# LDO.net
KiCad netlist of a schematic drawn in Altium Designer
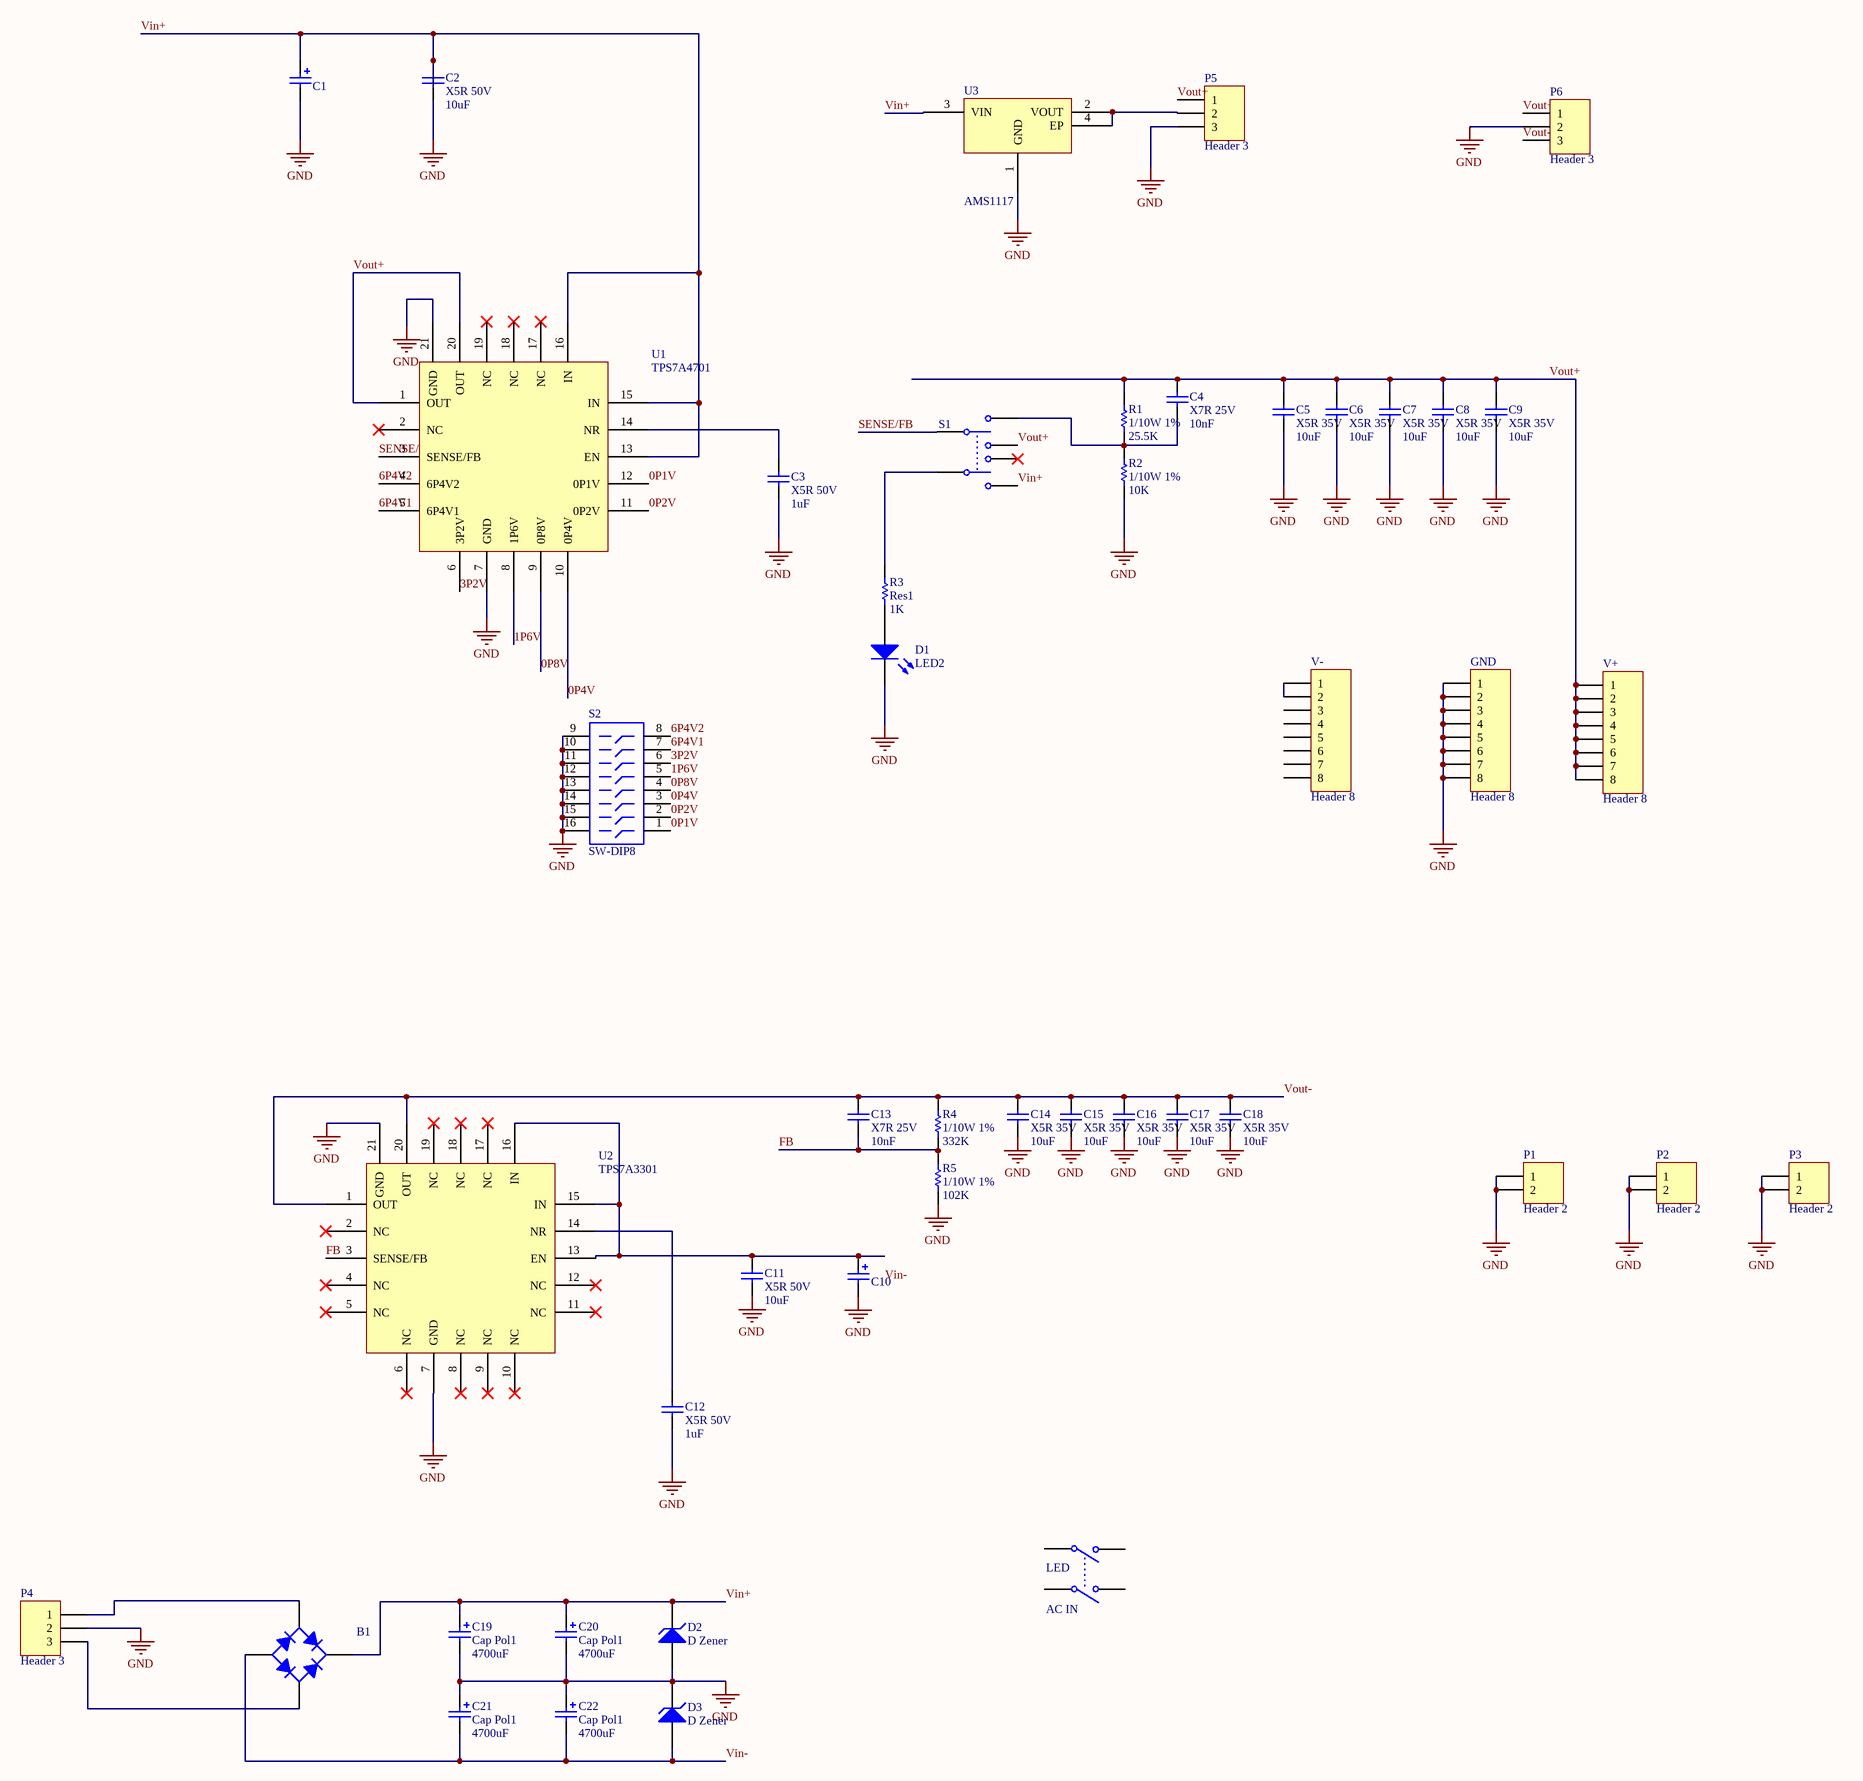
[diagram p0: LDO.SchDoc]

(export (version "E")
  (design (tool "Eeschema 10.0.6"))
  (components
    (comp (ref "AC IN")
      (value "SW AC 250V 6A")
      (footprint "SW AC 250V 6A")
      (libsource (lib "SMD") (part "SW AC 250V 6A"))
    )
    (comp (ref "B1")
      (value "Diode Bridge")
      (footprint "Diode Bridge")
      (libsource (lib "SMD") (part "Diode Bridge"))
    )
    (comp (ref "C1") (value "Tantalum") (footprint "D 7343-31") (libsource (lib "SMD") (part "Tantalum")))
    (comp (ref "C2")
      (value "X5R 50V")
      (footprint "C1206")
      (description "Capacitor (Semiconductor SIM Model)")
      (fields (field (name "ALTIUM_VALUE") "10uF") (field (name "PUBLISHER") "Altium Limited"))
      (libsource (lib "Miscellaneous Devices") (part "Cap Semi"))
    )
    (comp (ref "C3")
      (value "X5R 50V")
      (footprint "1608[0603]")
      (description "Capacitor")
      (fields (field (name "ALTIUM_VALUE") "1uF") (field (name "PUBLISHER") "Altium Limited"))
      (libsource (lib "Miscellaneous Devices") (part "Cap"))
    )
    (comp (ref "C4")
      (value "X7R 25V")
      (footprint "1608[0603]")
      (description "Capacitor")
      (fields (field (name "ALTIUM_VALUE") "10nF") (field (name "PUBLISHER") "Altium Limited"))
      (libsource (lib "Miscellaneous Devices") (part "Cap"))
    )
    (comp (ref "C5")
      (value "X5R 35V")
      (footprint "6-0805_N")
      (description "Capacitor")
      (fields (field (name "ALTIUM_VALUE") "10uF") (field (name "PUBLISHER") "Altium Limited"))
      (libsource (lib "Miscellaneous Devices") (part "Cap"))
    )
    (comp (ref "C6")
      (value "X5R 35V")
      (footprint "6-0805_N")
      (description "Capacitor")
      (fields (field (name "ALTIUM_VALUE") "10uF") (field (name "PUBLISHER") "Altium Limited"))
      (libsource (lib "Miscellaneous Devices") (part "Cap"))
    )
    (comp (ref "C7")
      (value "X5R 35V")
      (footprint "6-0805_N")
      (description "Capacitor")
      (fields (field (name "ALTIUM_VALUE") "10uF") (field (name "PUBLISHER") "Altium Limited"))
      (libsource (lib "Miscellaneous Devices") (part "Cap"))
    )
    (comp (ref "C8")
      (value "X5R 35V")
      (footprint "6-0805_N")
      (description "Capacitor")
      (fields (field (name "ALTIUM_VALUE") "10uF") (field (name "PUBLISHER") "Altium Limited"))
      (libsource (lib "Miscellaneous Devices") (part "Cap"))
    )
    (comp (ref "C9")
      (value "X5R 35V")
      (footprint "6-0805_N")
      (description "Capacitor")
      (fields (field (name "ALTIUM_VALUE") "10uF") (field (name "PUBLISHER") "Altium Limited"))
      (libsource (lib "Miscellaneous Devices") (part "Cap"))
    )
    (comp (ref "C10") (value "Tantalum") (footprint "D 7343-31") (libsource (lib "SMD") (part "Tantalum")))
    (comp (ref "C11")
      (value "X5R 50V")
      (footprint "C1206")
      (description "Capacitor (Semiconductor SIM Model)")
      (fields (field (name "ALTIUM_VALUE") "10uF") (field (name "PUBLISHER") "Altium Limited"))
      (libsource (lib "Miscellaneous Devices") (part "Cap Semi"))
    )
    (comp (ref "C12")
      (value "X5R 50V")
      (footprint "1608[0603]")
      (description "Capacitor")
      (fields (field (name "ALTIUM_VALUE") "1uF") (field (name "PUBLISHER") "Altium Limited"))
      (libsource (lib "Miscellaneous Devices") (part "Cap"))
    )
    (comp (ref "C13")
      (value "X7R 25V")
      (footprint "1608[0603]")
      (description "Capacitor")
      (fields (field (name "ALTIUM_VALUE") "10nF") (field (name "PUBLISHER") "Altium Limited"))
      (libsource (lib "Miscellaneous Devices") (part "Cap"))
    )
    (comp (ref "C14")
      (value "X5R 35V")
      (footprint "6-0805_N")
      (description "Capacitor")
      (fields (field (name "ALTIUM_VALUE") "10uF") (field (name "PUBLISHER") "Altium Limited"))
      (libsource (lib "Miscellaneous Devices") (part "Cap"))
    )
    (comp (ref "C15")
      (value "X5R 35V")
      (footprint "6-0805_N")
      (description "Capacitor")
      (fields (field (name "ALTIUM_VALUE") "10uF") (field (name "PUBLISHER") "Altium Limited"))
      (libsource (lib "Miscellaneous Devices") (part "Cap"))
    )
    (comp (ref "C16")
      (value "X5R 35V")
      (footprint "6-0805_N")
      (description "Capacitor")
      (fields (field (name "ALTIUM_VALUE") "10uF") (field (name "PUBLISHER") "Altium Limited"))
      (libsource (lib "Miscellaneous Devices") (part "Cap"))
    )
    (comp (ref "C17")
      (value "X5R 35V")
      (footprint "6-0805_N")
      (description "Capacitor")
      (fields (field (name "ALTIUM_VALUE") "10uF") (field (name "PUBLISHER") "Altium Limited"))
      (libsource (lib "Miscellaneous Devices") (part "Cap"))
    )
    (comp (ref "C18")
      (value "X5R 35V")
      (footprint "6-0805_N")
      (description "Capacitor")
      (fields (field (name "ALTIUM_VALUE") "10uF") (field (name "PUBLISHER") "Altium Limited"))
      (libsource (lib "Miscellaneous Devices") (part "Cap"))
    )
    (comp (ref "C19")
      (value "Cap Pol1")
      (footprint "RB7.6-15")
      (description "Polarized Capacitor (Radial)")
      (fields (field (name "ALTIUM_VALUE") "4700uF") (field (name "PUBLISHER") "Altium Limited"))
      (libsource (lib "Miscellaneous Devices") (part "Cap Pol1"))
    )
    (comp (ref "C20")
      (value "Cap Pol1")
      (footprint "RB7.6-15")
      (description "Polarized Capacitor (Radial)")
      (fields (field (name "ALTIUM_VALUE") "4700uF") (field (name "PUBLISHER") "Altium Limited"))
      (libsource (lib "Miscellaneous Devices") (part "Cap Pol1"))
    )
    (comp (ref "C21")
      (value "Cap Pol1")
      (footprint "RB7.6-15")
      (description "Polarized Capacitor (Radial)")
      (fields (field (name "ALTIUM_VALUE") "4700uF") (field (name "PUBLISHER") "Altium Limited"))
      (libsource (lib "Miscellaneous Devices") (part "Cap Pol1"))
    )
    (comp (ref "C22")
      (value "Cap Pol1")
      (footprint "RB7.6-15")
      (description "Polarized Capacitor (Radial)")
      (fields (field (name "ALTIUM_VALUE") "4700uF") (field (name "PUBLISHER") "Altium Limited"))
      (libsource (lib "Miscellaneous Devices") (part "Cap Pol1"))
    )
    (comp (ref "D1")
      (value "LED2")
      (footprint "6-0805_N")
      (description "Typical RED, GREEN, YELLOW, AMBER GaAs LED")
      (fields (field (name "PUBLISHER") "Altium Limited"))
      (libsource (lib "Miscellaneous Devices") (part "LED2"))
    )
    (comp (ref "D2")
      (value "D Zener")
      (footprint "AXIAL-0.3")
      (description "Zener Diode")
      (fields (field (name "PUBLISHER") "Altium Limited"))
      (libsource (lib "Miscellaneous Devices") (part "D Zener"))
    )
    (comp (ref "D3")
      (value "D Zener")
      (footprint "AXIAL-0.3")
      (description "Zener Diode")
      (fields (field (name "PUBLISHER") "Altium Limited"))
      (libsource (lib "Miscellaneous Devices") (part "D Zener"))
    )
    (comp (ref "GND")
      (value "Header 8")
      (footprint "HDR1X8")
      (description "Header, 8-Pin")
      (fields (field (name "PUBLISHER") "Altium Limited"))
      (libsource (lib "Miscellaneous Connectors") (part "Header 8"))
    )
    (comp (ref "P1")
      (value "Header 2")
      (footprint "HDR1X2")
      (description "Header, 2-Pin")
      (fields (field (name "PUBLISHER") "Altium Limited"))
      (libsource (lib "Miscellaneous Connectors") (part "Header 2"))
    )
    (comp (ref "P2")
      (value "Header 2")
      (footprint "HDR1X2")
      (description "Header, 2-Pin")
      (fields (field (name "PUBLISHER") "Altium Limited"))
      (libsource (lib "Miscellaneous Connectors") (part "Header 2"))
    )
    (comp (ref "P3")
      (value "Header 2")
      (footprint "HDR1X2")
      (description "Header, 2-Pin")
      (fields (field (name "PUBLISHER") "Altium Limited"))
      (libsource (lib "Miscellaneous Connectors") (part "Header 2"))
    )
    (comp (ref "P4")
      (value "Header 3")
      (footprint "HDR1X3")
      (description "Header, 3-Pin")
      (fields (field (name "PUBLISHER") "Altium Limited"))
      (libsource (lib "") (part "Header 3_1"))
    )
    (comp (ref "P5")
      (value "Header 3")
      (footprint "HDR1X3")
      (description "Header, 3-Pin")
      (fields (field (name "PUBLISHER") "Altium Limited"))
      (libsource (lib "Miscellaneous Connectors") (part "Header 3"))
    )
    (comp (ref "P6")
      (value "Header 3")
      (footprint "HDR1X3")
      (description "Header, 3-Pin")
      (fields (field (name "PUBLISHER") "Altium Limited"))
      (libsource (lib "Miscellaneous Connectors") (part "Header 3"))
    )
    (comp (ref "R1")
      (value "1/10W 1%")
      (footprint "1608[0603]")
      (description "Resistor")
      (fields (field (name "ALTIUM_VALUE") "25.5K") (field (name "PUBLISHER") "Altium Limited"))
      (libsource (lib "Miscellaneous Devices") (part "Res1"))
    )
    (comp (ref "R2")
      (value "1/10W 1%")
      (footprint "1608[0603]")
      (description "Resistor")
      (fields (field (name "ALTIUM_VALUE") "10K") (field (name "PUBLISHER") "Altium Limited"))
      (libsource (lib "Miscellaneous Devices") (part "Res1"))
    )
    (comp (ref "R3")
      (value "Res1")
      (footprint "6-0805_N")
      (description "Resistor")
      (fields (field (name "ALTIUM_VALUE") "1K") (field (name "PUBLISHER") "Altium Limited"))
      (libsource (lib "Miscellaneous Devices") (part "Res1"))
    )
    (comp (ref "R4")
      (value "1/10W 1%")
      (footprint "1608[0603]")
      (description "Resistor")
      (fields (field (name "ALTIUM_VALUE") "332K") (field (name "PUBLISHER") "Altium Limited"))
      (libsource (lib "Miscellaneous Devices") (part "Res1"))
    )
    (comp (ref "R5")
      (value "1/10W 1%")
      (footprint "1608[0603]")
      (description "Resistor")
      (fields (field (name "ALTIUM_VALUE") "102K") (field (name "PUBLISHER") "Altium Limited"))
      (libsource (lib "Miscellaneous Devices") (part "Res1"))
    )
    (comp (ref "S1") (value "SW  Press") (footprint "SW Press") (libsource (lib "SMD") (part "SW  Press")))
    (comp (ref "S2")
      (value "SW-DIP8")
      (footprint "DIP-16-KEY")
      (description "4009 Series DIP Switch, Raised actuator")
      (fields (field (name "PUBLISHER") "Altium Limited"))
      (libsource (lib "Miscellaneous Devices") (part "SW-DIP8"))
    )
    (comp (ref "U1")
      (value "TPS7A4701")
      (footprint "RGW 5×5 QFN-20")
      (libsource (lib "Created") (part "TPS7A4701RGWT"))
    )
    (comp (ref "U2")
      (value "TPS7A3301")
      (footprint "RGW 5×5 QFN-20")
      (libsource (lib "Created") (part "TPS7A3301RGWT"))
    )
    (comp (ref "U3") (value "AMS1117") (footprint "SOT223_N") (libsource (lib "Created") (part "AMS1117")))
    (comp (ref "V+")
      (value "Header 8")
      (footprint "HDR1X8")
      (description "Header, 8-Pin")
      (fields (field (name "PUBLISHER") "Altium Limited"))
      (libsource (lib "Miscellaneous Connectors") (part "Header 8"))
    )
    (comp (ref "V-")
      (value "Header 8")
      (footprint "HDR1X8")
      (description "Header, 8-Pin")
      (fields (field (name "PUBLISHER") "Altium Limited"))
      (libsource (lib "Miscellaneous Connectors") (part "Header 8"))
    )
  )
  (nets
    (net (code "1") (name "/0P1V") (class "Default")
      (node (ref "S2") (pin "1") (pinfunction "1_1") (pintype "passive"))
      (node (ref "U1") (pin "12") (pinfunction "0P1V_12") (pintype "passive"))
    )
    (net (code "2") (name "/0P2V") (class "Default")
      (node (ref "S2") (pin "2") (pinfunction "2_2") (pintype "passive"))
      (node (ref "U1") (pin "11") (pinfunction "0P2V_11") (pintype "passive"))
    )
    (net (code "3") (name "/0P4V") (class "Default")
      (node (ref "S2") (pin "3") (pinfunction "3_3") (pintype "passive"))
      (node (ref "U1") (pin "10") (pinfunction "0P4V_10") (pintype "passive"))
    )
    (net (code "4") (name "/0P8V") (class "Default")
      (node (ref "S2") (pin "4") (pinfunction "4_4") (pintype "passive"))
      (node (ref "U1") (pin "9") (pinfunction "0P8V_9") (pintype "passive"))
    )
    (net (code "5") (name "/1P6V") (class "Default")
      (node (ref "S2") (pin "5") (pinfunction "5_5") (pintype "passive"))
      (node (ref "U1") (pin "8") (pinfunction "1P6V_8") (pintype "passive"))
    )
    (net (code "6") (name "/3P2V") (class "Default")
      (node (ref "S2") (pin "6") (pinfunction "6_6") (pintype "passive"))
      (node (ref "U1") (pin "6") (pinfunction "3P2V_6") (pintype "passive"))
    )
    (net (code "7") (name "/6P4V1") (class "Default")
      (node (ref "S2") (pin "7") (pinfunction "7_7") (pintype "passive"))
      (node (ref "U1") (pin "5") (pinfunction "6P4V1_5") (pintype "passive"))
    )
    (net (code "8") (name "/6P4V2") (class "Default")
      (node (ref "S2") (pin "8") (pinfunction "8_8") (pintype "passive"))
      (node (ref "U1") (pin "4") (pinfunction "6P4V2_4") (pintype "passive"))
    )
    (net (code "9") (name "/FB") (class "Default")
      (node (ref "C13") (pin "1") (pinfunction "1_1") (pintype "passive"))
      (node (ref "R4") (pin "1") (pinfunction "1_1") (pintype "passive"))
      (node (ref "R5") (pin "2") (pinfunction "2_2") (pintype "passive"))
      (node (ref "U2") (pin "3") (pinfunction "SENSE/FB_3") (pintype "passive"))
    )
    (net (code "10") (name "/SENSE{slash}FB") (class "Default")
      (node (ref "S1") (pin "3") (pinfunction "3_3") (pintype "passive"))
      (node (ref "U1") (pin "3") (pinfunction "SENSE/FB_3") (pintype "passive"))
    )
    (net (code "11") (name "/Vin+") (class "Default")
      (node (ref "B1") (pin "4") (pinfunction "4_4") (pintype "passive"))
      (node (ref "C1") (pin "1") (pinfunction "1_1") (pintype "passive"))
      (node (ref "C19") (pin "1") (pinfunction "1_1") (pintype "passive"))
      (node (ref "C2") (pin "2") (pinfunction "2_2") (pintype "passive"))
      (node (ref "C20") (pin "1") (pinfunction "1_1") (pintype "passive"))
      (node (ref "D2") (pin "2") (pinfunction "K_2") (pintype "passive"))
      (node (ref "S1") (pin "5") (pinfunction "5_5") (pintype "passive"))
      (node (ref "U1") (pin "13") (pinfunction "EN_13") (pintype "passive"))
      (node (ref "U1") (pin "15") (pinfunction "IN_15") (pintype "passive"))
      (node (ref "U1") (pin "16") (pinfunction "IN_16") (pintype "passive"))
      (node (ref "U3") (pin "3") (pinfunction "VIN_3") (pintype "passive"))
    )
    (net (code "12") (name "/Vin-") (class "Default")
      (node (ref "B1") (pin "1") (pinfunction "1_1") (pintype "passive"))
      (node (ref "C21") (pin "2") (pinfunction "2_2") (pintype "passive"))
      (node (ref "C22") (pin "2") (pinfunction "2_2") (pintype "passive"))
      (node (ref "D3") (pin "1") (pinfunction "A_1") (pintype "passive"))
    )
    (net (code "13") (name "/Vout+") (class "Default")
      (node (ref "C4") (pin "2") (pinfunction "2_2") (pintype "passive"))
      (node (ref "C5") (pin "2") (pinfunction "2_2") (pintype "passive"))
      (node (ref "C6") (pin "2") (pinfunction "2_2") (pintype "passive"))
      (node (ref "C7") (pin "2") (pinfunction "2_2") (pintype "passive"))
      (node (ref "C8") (pin "2") (pinfunction "2_2") (pintype "passive"))
      (node (ref "C9") (pin "2") (pinfunction "2_2") (pintype "passive"))
      (node (ref "P5") (pin "1") (pinfunction "1_1") (pintype "passive"))
      (node (ref "P6") (pin "1") (pinfunction "1_1") (pintype "passive"))
      (node (ref "R1") (pin "2") (pinfunction "2_2") (pintype "passive"))
      (node (ref "S1") (pin "2") (pinfunction "2_2") (pintype "passive"))
      (node (ref "U1") (pin "1") (pinfunction "OUT_1") (pintype "passive"))
      (node (ref "U1") (pin "20") (pinfunction "OUT_20") (pintype "passive"))
      (node (ref "V+") (pin "1") (pinfunction "1_1") (pintype "passive"))
      (node (ref "V+") (pin "2") (pinfunction "2_2") (pintype "passive"))
      (node (ref "V+") (pin "3") (pinfunction "3_3") (pintype "passive"))
      (node (ref "V+") (pin "4") (pinfunction "4_4") (pintype "passive"))
      (node (ref "V+") (pin "5") (pinfunction "5_5") (pintype "passive"))
      (node (ref "V+") (pin "6") (pinfunction "6_6") (pintype "passive"))
      (node (ref "V+") (pin "7") (pinfunction "7_7") (pintype "passive"))
      (node (ref "V+") (pin "8") (pinfunction "8_8") (pintype "passive"))
    )
    (net (code "14") (name "/Vout-") (class "Default")
      (node (ref "C13") (pin "2") (pinfunction "2_2") (pintype "passive"))
      (node (ref "C14") (pin "2") (pinfunction "2_2") (pintype "passive"))
      (node (ref "C15") (pin "2") (pinfunction "2_2") (pintype "passive"))
      (node (ref "C16") (pin "2") (pinfunction "2_2") (pintype "passive"))
      (node (ref "C17") (pin "2") (pinfunction "2_2") (pintype "passive"))
      (node (ref "C18") (pin "2") (pinfunction "2_2") (pintype "passive"))
      (node (ref "P6") (pin "3") (pinfunction "3_3") (pintype "passive"))
      (node (ref "R4") (pin "2") (pinfunction "2_2") (pintype "passive"))
      (node (ref "U2") (pin "1") (pinfunction "OUT_1") (pintype "passive"))
      (node (ref "U2") (pin "20") (pinfunction "OUT_20") (pintype "passive"))
    )
    (net (code "15") (name "GND") (class "Default")
      (node (ref "C1") (pin "2") (pinfunction "2_2") (pintype "passive"))
      (node (ref "C10") (pin "2") (pinfunction "2_2") (pintype "passive"))
      (node (ref "C11") (pin "1") (pinfunction "1_1") (pintype "passive"))
      (node (ref "C12") (pin "1") (pinfunction "1_1") (pintype "passive"))
      (node (ref "C14") (pin "1") (pinfunction "1_1") (pintype "passive"))
      (node (ref "C15") (pin "1") (pinfunction "1_1") (pintype "passive"))
      (node (ref "C16") (pin "1") (pinfunction "1_1") (pintype "passive"))
      (node (ref "C17") (pin "1") (pinfunction "1_1") (pintype "passive"))
      (node (ref "C18") (pin "1") (pinfunction "1_1") (pintype "passive"))
      (node (ref "C19") (pin "2") (pinfunction "2_2") (pintype "passive"))
      (node (ref "C2") (pin "1") (pinfunction "1_1") (pintype "passive"))
      (node (ref "C20") (pin "2") (pinfunction "2_2") (pintype "passive"))
      (node (ref "C21") (pin "1") (pinfunction "1_1") (pintype "passive"))
      (node (ref "C22") (pin "1") (pinfunction "1_1") (pintype "passive"))
      (node (ref "C3") (pin "1") (pinfunction "1_1") (pintype "passive"))
      (node (ref "C5") (pin "1") (pinfunction "1_1") (pintype "passive"))
      (node (ref "C6") (pin "1") (pinfunction "1_1") (pintype "passive"))
      (node (ref "C7") (pin "1") (pinfunction "1_1") (pintype "passive"))
      (node (ref "C8") (pin "1") (pinfunction "1_1") (pintype "passive"))
      (node (ref "C9") (pin "1") (pinfunction "1_1") (pintype "passive"))
      (node (ref "D1") (pin "2") (pinfunction "K_2") (pintype "passive"))
      (node (ref "D2") (pin "1") (pinfunction "A_1") (pintype "passive"))
      (node (ref "D3") (pin "2") (pinfunction "K_2") (pintype "passive"))
      (node (ref "GND") (pin "1") (pinfunction "1_1") (pintype "passive"))
      (node (ref "GND") (pin "2") (pinfunction "2_2") (pintype "passive"))
      (node (ref "GND") (pin "3") (pinfunction "3_3") (pintype "passive"))
      (node (ref "GND") (pin "4") (pinfunction "4_4") (pintype "passive"))
      (node (ref "GND") (pin "5") (pinfunction "5_5") (pintype "passive"))
      (node (ref "GND") (pin "6") (pinfunction "6_6") (pintype "passive"))
      (node (ref "GND") (pin "7") (pinfunction "7_7") (pintype "passive"))
      (node (ref "GND") (pin "8") (pinfunction "8_8") (pintype "passive"))
      (node (ref "P1") (pin "1") (pinfunction "1_1") (pintype "passive"))
      (node (ref "P1") (pin "2") (pinfunction "2_2") (pintype "passive"))
      (node (ref "P2") (pin "1") (pinfunction "1_1") (pintype "passive"))
      (node (ref "P2") (pin "2") (pinfunction "2_2") (pintype "passive"))
      (node (ref "P3") (pin "1") (pinfunction "1_1") (pintype "passive"))
      (node (ref "P3") (pin "2") (pinfunction "2_2") (pintype "passive"))
      (node (ref "P4") (pin "2") (pinfunction "2_2") (pintype "passive"))
      (node (ref "P5") (pin "3") (pinfunction "3_3") (pintype "passive"))
      (node (ref "P6") (pin "2") (pinfunction "2_2") (pintype "passive"))
      (node (ref "R2") (pin "1") (pinfunction "1_1") (pintype "passive"))
      (node (ref "R5") (pin "1") (pinfunction "1_1") (pintype "passive"))
      (node (ref "S2") (pin "10") (pinfunction "10_10") (pintype "passive"))
      (node (ref "S2") (pin "11") (pinfunction "11_11") (pintype "passive"))
      (node (ref "S2") (pin "12") (pinfunction "12_12") (pintype "passive"))
      (node (ref "S2") (pin "13") (pinfunction "13_13") (pintype "passive"))
      (node (ref "S2") (pin "14") (pinfunction "14_14") (pintype "passive"))
      (node (ref "S2") (pin "15") (pinfunction "15_15") (pintype "passive"))
      (node (ref "S2") (pin "16") (pinfunction "16_16") (pintype "passive"))
      (node (ref "S2") (pin "9") (pinfunction "9_9") (pintype "passive"))
      (node (ref "U1") (pin "21") (pinfunction "GND_21") (pintype "passive"))
      (node (ref "U1") (pin "7") (pinfunction "GND_7") (pintype "passive"))
      (node (ref "U2") (pin "21") (pinfunction "GND_21") (pintype "passive"))
      (node (ref "U2") (pin "7") (pinfunction "GND_7") (pintype "passive"))
      (node (ref "U3") (pin "1") (pinfunction "GND_1") (pintype "passive"))
    )
    (net (code "16") (name "Net-(B1-Pad2)") (class "Default")
      (node (ref "B1") (pin "2") (pinfunction "2_2") (pintype "passive"))
      (node (ref "P4") (pin "1") (pinfunction "1_1") (pintype "passive"))
    )
    (net (code "17") (name "Net-(B1-Pad3)") (class "Default")
      (node (ref "B1") (pin "3") (pinfunction "3_3") (pintype "passive"))
      (node (ref "P4") (pin "3") (pinfunction "3_3") (pintype "passive"))
    )
    (net (code "18") (name "Net-(C4-Pad1)") (class "Default")
      (node (ref "C4") (pin "1") (pinfunction "1_1") (pintype "passive"))
      (node (ref "R1") (pin "1") (pinfunction "1_1") (pintype "passive"))
      (node (ref "R2") (pin "2") (pinfunction "2_2") (pintype "passive"))
      (node (ref "S1") (pin "1") (pinfunction "1_1") (pintype "passive"))
    )
    (net (code "19") (name "Net-(D1-A)") (class "Default")
      (node (ref "D1") (pin "1") (pinfunction "A_1") (pintype "passive"))
      (node (ref "R3") (pin "1") (pinfunction "1_1") (pintype "passive"))
    )
    (net (code "20") (name "Net-(R3-Pad2)") (class "Default")
      (node (ref "R3") (pin "2") (pinfunction "2_2") (pintype "passive"))
      (node (ref "S1") (pin "6") (pinfunction "6_6") (pintype "passive"))
    )
    (net (code "21") (name "Net-(U1-NR)") (class "Default")
      (node (ref "C3") (pin "2") (pinfunction "2_2") (pintype "passive"))
      (node (ref "U1") (pin "14") (pinfunction "NR_14") (pintype "passive"))
    )
    (net (code "22") (name "Net-(U2-EN)") (class "Default")
      (node (ref "C10") (pin "1") (pinfunction "1_1") (pintype "passive"))
      (node (ref "C11") (pin "2") (pinfunction "2_2") (pintype "passive"))
      (node (ref "U2") (pin "13") (pinfunction "EN_13") (pintype "passive"))
      (node (ref "U2") (pin "15") (pinfunction "IN_15") (pintype "passive"))
      (node (ref "U2") (pin "16") (pinfunction "IN_16") (pintype "passive"))
    )
    (net (code "23") (name "Net-(U2-NR)") (class "Default")
      (node (ref "C12") (pin "2") (pinfunction "2_2") (pintype "passive"))
      (node (ref "U2") (pin "14") (pinfunction "NR_14") (pintype "passive"))
    )
    (net (code "24") (name "Net-(U3-EP)") (class "Default")
      (node (ref "P5") (pin "2") (pinfunction "2_2") (pintype "passive"))
      (node (ref "U3") (pin "2") (pinfunction "VOUT_2") (pintype "passive"))
      (node (ref "U3") (pin "4") (pinfunction "EP_4") (pintype "passive"))
    )
    (net (code "25") (name "Net-(V--Pad1)") (class "Default")
      (node (ref "V-") (pin "1") (pinfunction "1_1") (pintype "passive"))
      (node (ref "V-") (pin "2") (pinfunction "2_2") (pintype "passive"))
    )
    (net (code "26") (name "unconnected-(AC IN-Pad1)") (class "Default")
      (node (ref "AC IN") (pin "1") (pinfunction "1_1") (pintype "passive"))
    )
    (net (code "27") (name "unconnected-(AC IN-Pad2)") (class "Default")
      (node (ref "AC IN") (pin "2") (pinfunction "2_2") (pintype "passive"))
    )
    (net (code "28") (name "unconnected-(AC IN-Pad3)") (class "Default")
      (node (ref "AC IN") (pin "3") (pinfunction "3_3") (pintype "passive"))
    )
    (net (code "29") (name "unconnected-(AC IN-Pad4)") (class "Default")
      (node (ref "AC IN") (pin "4") (pinfunction "4_4") (pintype "passive"))
    )
    (net (code "30") (name "unconnected-(S1-Pad4)") (class "Default")
      (node (ref "S1") (pin "4") (pinfunction "4_4") (pintype "passive+no_connect"))
    )
    (net (code "31") (name "unconnected-(U1-NC-Pad2)") (class "Default")
      (node (ref "U1") (pin "2") (pinfunction "NC_2") (pintype "passive+no_connect"))
    )
    (net (code "32") (name "unconnected-(U1-NC-Pad17)") (class "Default")
      (node (ref "U1") (pin "17") (pinfunction "NC_17") (pintype "passive+no_connect"))
    )
    (net (code "33") (name "unconnected-(U1-NC-Pad18)") (class "Default")
      (node (ref "U1") (pin "18") (pinfunction "NC_18") (pintype "passive+no_connect"))
    )
    (net (code "34") (name "unconnected-(U1-NC-Pad19)") (class "Default")
      (node (ref "U1") (pin "19") (pinfunction "NC_19") (pintype "passive+no_connect"))
    )
    (net (code "35") (name "unconnected-(U2-NC-Pad2)") (class "Default")
      (node (ref "U2") (pin "2") (pinfunction "NC_2") (pintype "passive+no_connect"))
    )
    (net (code "36") (name "unconnected-(U2-NC-Pad4)") (class "Default")
      (node (ref "U2") (pin "4") (pinfunction "NC_4") (pintype "passive+no_connect"))
    )
    (net (code "37") (name "unconnected-(U2-NC-Pad5)") (class "Default")
      (node (ref "U2") (pin "5") (pinfunction "NC_5") (pintype "passive+no_connect"))
    )
    (net (code "38") (name "unconnected-(U2-NC-Pad6)") (class "Default")
      (node (ref "U2") (pin "6") (pinfunction "NC_6") (pintype "passive+no_connect"))
    )
    (net (code "39") (name "unconnected-(U2-NC-Pad8)") (class "Default")
      (node (ref "U2") (pin "8") (pinfunction "NC_8") (pintype "passive+no_connect"))
    )
    (net (code "40") (name "unconnected-(U2-NC-Pad9)") (class "Default")
      (node (ref "U2") (pin "9") (pinfunction "NC_9") (pintype "passive+no_connect"))
    )
    (net (code "41") (name "unconnected-(U2-NC-Pad10)") (class "Default")
      (node (ref "U2") (pin "10") (pinfunction "NC_10") (pintype "passive+no_connect"))
    )
    (net (code "42") (name "unconnected-(U2-NC-Pad11)") (class "Default")
      (node (ref "U2") (pin "11") (pinfunction "NC_11") (pintype "passive+no_connect"))
    )
    (net (code "43") (name "unconnected-(U2-NC-Pad12)") (class "Default")
      (node (ref "U2") (pin "12") (pinfunction "NC_12") (pintype "passive+no_connect"))
    )
    (net (code "44") (name "unconnected-(U2-NC-Pad17)") (class "Default")
      (node (ref "U2") (pin "17") (pinfunction "NC_17") (pintype "passive+no_connect"))
    )
    (net (code "45") (name "unconnected-(U2-NC-Pad18)") (class "Default")
      (node (ref "U2") (pin "18") (pinfunction "NC_18") (pintype "passive+no_connect"))
    )
    (net (code "46") (name "unconnected-(U2-NC-Pad19)") (class "Default")
      (node (ref "U2") (pin "19") (pinfunction "NC_19") (pintype "passive+no_connect"))
    )
    (net (code "47") (name "unconnected-(V--Pad3)") (class "Default")
      (node (ref "V-") (pin "3") (pinfunction "3_3") (pintype "passive"))
    )
    (net (code "48") (name "unconnected-(V--Pad4)") (class "Default")
      (node (ref "V-") (pin "4") (pinfunction "4_4") (pintype "passive"))
    )
    (net (code "49") (name "unconnected-(V--Pad5)") (class "Default")
      (node (ref "V-") (pin "5") (pinfunction "5_5") (pintype "passive"))
    )
    (net (code "50") (name "unconnected-(V--Pad6)") (class "Default")
      (node (ref "V-") (pin "6") (pinfunction "6_6") (pintype "passive"))
    )
    (net (code "51") (name "unconnected-(V--Pad7)") (class "Default")
      (node (ref "V-") (pin "7") (pinfunction "7_7") (pintype "passive"))
    )
    (net (code "52") (name "unconnected-(V--Pad8)") (class "Default")
      (node (ref "V-") (pin "8") (pinfunction "8_8") (pintype "passive"))
    )
  )
)
